# SCHEMATICS1.net
KiCad netlist of a schematic drawn in EasyEDA
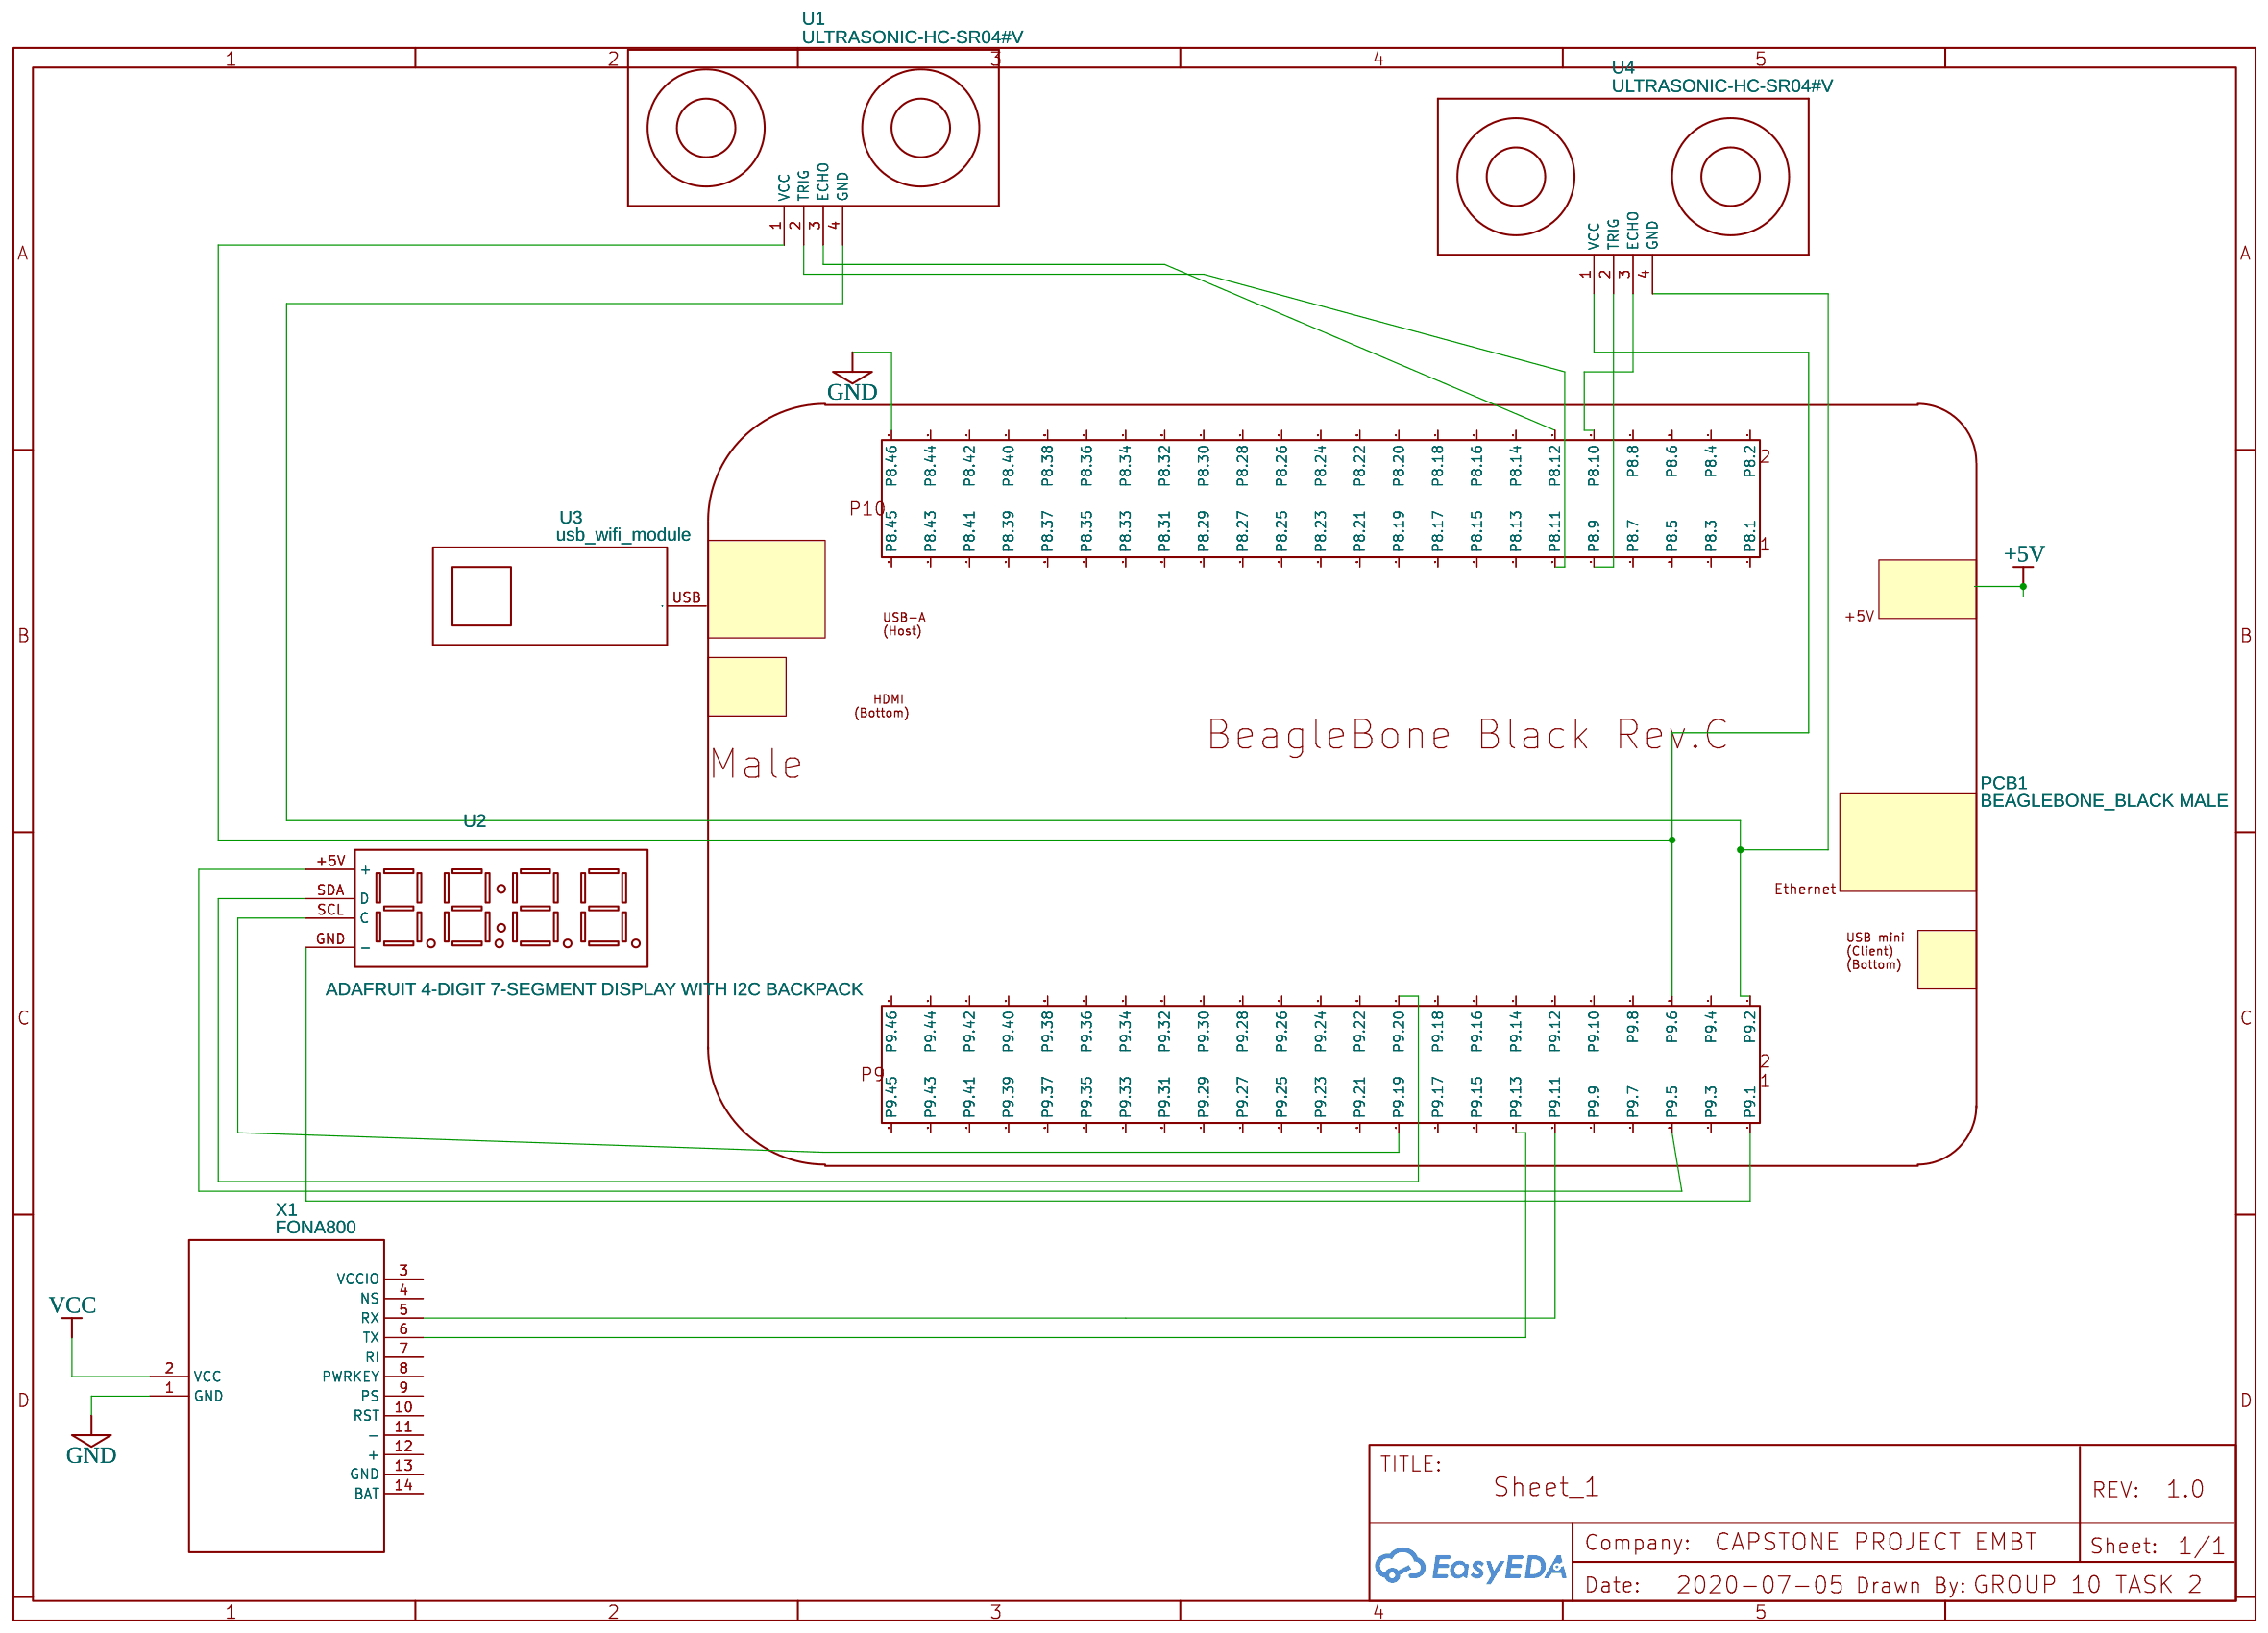
[diagram p0: schematic sheet]

(export (version "E")
  (design (tool "Eeschema 10.0.6"))
  (components
    (comp (ref "PCB1") (value "BEAGLEBONE_BLACK MALE") (libsource (lib "") (part "BEAGLEBONE_BLACK MALE")))
    (comp (ref "U1") (value "ULTRASONIC-HC-SR04#V") (libsource (lib "") (part "ULTRASONIC-HC-SR04#V")))
    (comp (ref "U2")
      (value "ADAFRUIT 4-DIGIT 7-SEGMENT DISPLAY WITH I2C BACKPACK")
      (libsource (lib "") (part "ADAFRUIT 4-DIGIT 7-SEGMENT DISPLAY WITH I2C BACKPACK"))
    )
    (comp (ref "U3")
      (value "usb_wifi_module")
      (fields (field (name "BOM_Manufacturer Part") "usb wifi module"))
      (libsource (lib "") (part "usb_wifi_module"))
    )
    (comp (ref "U4") (value "ULTRASONIC-HC-SR04#V") (libsource (lib "") (part "ULTRASONIC-HC-SR04#V")))
    (comp (ref "X1") (value "FONA800") (libsource (lib "") (part "FONA800")))
  )
  (nets
    (net (code "2") (name "GND") (class "Default")
      (node (ref "PCB1") (pin "P8.46") (pinfunction "P8.46_P8.46") (pintype "bidirectional"))
      (node (ref "X1") (pin "1") (pinfunction "GND_1") (pintype "unspecified"))
    )
    (net (code "3") (name "Net-(U1-ECHO)") (class "Default")
      (node (ref "PCB1") (pin "P8.12") (pinfunction "P8.12_P8.12") (pintype "bidirectional"))
      (node (ref "U1") (pin "3") (pinfunction "ECHO_3") (pintype "output"))
    )
    (net (code "4") (name "Net-(U1-GND)") (class "Default")
      (node (ref "PCB1") (pin "P9.2") (pinfunction "P9.2_P9.2") (pintype "bidirectional"))
      (node (ref "U1") (pin "4") (pinfunction "GND_4") (pintype "passive"))
      (node (ref "U4") (pin "4") (pinfunction "GND_4") (pintype "passive"))
    )
    (net (code "5") (name "Net-(U1-TRIG)") (class "Default")
      (node (ref "PCB1") (pin "P8.11") (pinfunction "P8.11_P8.11") (pintype "bidirectional"))
      (node (ref "U1") (pin "2") (pinfunction "TRIG_2") (pintype "input"))
    )
    (net (code "6") (name "Net-(U1-VCC)") (class "Default")
      (node (ref "PCB1") (pin "P9.6") (pinfunction "P9.6_P9.6") (pintype "bidirectional"))
      (node (ref "U1") (pin "1") (pinfunction "VCC_1") (pintype "passive"))
      (node (ref "U4") (pin "1") (pinfunction "VCC_1") (pintype "passive"))
    )
    (net (code "7") (name "Net-(U2-+)") (class "Default")
      (node (ref "PCB1") (pin "P9.5") (pinfunction "P9.5_P9.5") (pintype "bidirectional"))
      (node (ref "U2") (pin "+5V") (pinfunction "+_+5V") (pintype "unspecified"))
    )
    (net (code "8") (name "Net-(U2--)") (class "Default")
      (node (ref "PCB1") (pin "P9.1") (pinfunction "P9.1_P9.1") (pintype "bidirectional"))
      (node (ref "U2") (pin "GND") (pinfunction "-_GND") (pintype "unspecified"))
    )
    (net (code "9") (name "Net-(U2-C)") (class "Default")
      (node (ref "PCB1") (pin "P9.19") (pinfunction "P9.19_P9.19") (pintype "bidirectional"))
      (node (ref "U2") (pin "SCL") (pinfunction "C_SCL") (pintype "unspecified"))
    )
    (net (code "10") (name "Net-(U2-D)") (class "Default")
      (node (ref "PCB1") (pin "P9.20") (pinfunction "P9.20_P9.20") (pintype "bidirectional"))
      (node (ref "U2") (pin "SDA") (pinfunction "D_SDA") (pintype "unspecified"))
    )
    (net (code "11") (name "Net-(U4-ECHO)") (class "Default")
      (node (ref "PCB1") (pin "P8.10") (pinfunction "P8.10_P8.10") (pintype "bidirectional"))
      (node (ref "U4") (pin "3") (pinfunction "ECHO_3") (pintype "output"))
    )
    (net (code "12") (name "Net-(U4-TRIG)") (class "Default")
      (node (ref "PCB1") (pin "P8.9") (pinfunction "P8.9_P8.9") (pintype "bidirectional"))
      (node (ref "U4") (pin "2") (pinfunction "TRIG_2") (pintype "input"))
    )
    (net (code "13") (name "Net-(X1-RX)") (class "Default")
      (node (ref "PCB1") (pin "P9.11") (pinfunction "P9.11_P9.11") (pintype "bidirectional"))
      (node (ref "X1") (pin "5") (pinfunction "RX_5") (pintype "unspecified"))
    )
    (net (code "14") (name "Net-(X1-TX)") (class "Default")
      (node (ref "PCB1") (pin "P9.13") (pinfunction "P9.13_P9.13") (pintype "bidirectional"))
      (node (ref "X1") (pin "6") (pinfunction "TX_6") (pintype "unspecified"))
    )
    (net (code "15") (name "VCC") (class "Default")
      (node (ref "X1") (pin "2") (pinfunction "VCC_2") (pintype "unspecified"))
    )
    (net (code "16") (name "unconnected-(PCB1-PadP8.1)") (class "Default")
      (node (ref "PCB1") (pin "P8.1") (pinfunction "P8.1_P8.1") (pintype "bidirectional"))
    )
    (net (code "17") (name "unconnected-(PCB1-PadP8.2)") (class "Default")
      (node (ref "PCB1") (pin "P8.2") (pinfunction "P8.2_P8.2") (pintype "bidirectional"))
    )
    (net (code "18") (name "unconnected-(PCB1-PadP8.3)") (class "Default")
      (node (ref "PCB1") (pin "P8.3") (pinfunction "P8.3_P8.3") (pintype "bidirectional"))
    )
    (net (code "19") (name "unconnected-(PCB1-PadP8.4)") (class "Default")
      (node (ref "PCB1") (pin "P8.4") (pinfunction "P8.4_P8.4") (pintype "bidirectional"))
    )
    (net (code "20") (name "unconnected-(PCB1-PadP8.5)") (class "Default")
      (node (ref "PCB1") (pin "P8.5") (pinfunction "P8.5_P8.5") (pintype "bidirectional"))
    )
    (net (code "21") (name "unconnected-(PCB1-PadP8.6)") (class "Default")
      (node (ref "PCB1") (pin "P8.6") (pinfunction "P8.6_P8.6") (pintype "bidirectional"))
    )
    (net (code "22") (name "unconnected-(PCB1-PadP8.7)") (class "Default")
      (node (ref "PCB1") (pin "P8.7") (pinfunction "P8.7_P8.7") (pintype "bidirectional"))
    )
    (net (code "23") (name "unconnected-(PCB1-PadP8.8)") (class "Default")
      (node (ref "PCB1") (pin "P8.8") (pinfunction "P8.8_P8.8") (pintype "bidirectional"))
    )
    (net (code "24") (name "unconnected-(PCB1-PadP8.13)") (class "Default")
      (node (ref "PCB1") (pin "P8.13") (pinfunction "P8.13_P8.13") (pintype "bidirectional"))
    )
    (net (code "25") (name "unconnected-(PCB1-PadP8.14)") (class "Default")
      (node (ref "PCB1") (pin "P8.14") (pinfunction "P8.14_P8.14") (pintype "bidirectional"))
    )
    (net (code "26") (name "unconnected-(PCB1-PadP8.15)") (class "Default")
      (node (ref "PCB1") (pin "P8.15") (pinfunction "P8.15_P8.15") (pintype "bidirectional"))
    )
    (net (code "27") (name "unconnected-(PCB1-PadP8.16)") (class "Default")
      (node (ref "PCB1") (pin "P8.16") (pinfunction "P8.16_P8.16") (pintype "bidirectional"))
    )
    (net (code "28") (name "unconnected-(PCB1-PadP8.17)") (class "Default")
      (node (ref "PCB1") (pin "P8.17") (pinfunction "P8.17_P8.17") (pintype "bidirectional"))
    )
    (net (code "29") (name "unconnected-(PCB1-PadP8.18)") (class "Default")
      (node (ref "PCB1") (pin "P8.18") (pinfunction "P8.18_P8.18") (pintype "bidirectional"))
    )
    (net (code "30") (name "unconnected-(PCB1-PadP8.19)") (class "Default")
      (node (ref "PCB1") (pin "P8.19") (pinfunction "P8.19_P8.19") (pintype "bidirectional"))
    )
    (net (code "31") (name "unconnected-(PCB1-PadP8.20)") (class "Default")
      (node (ref "PCB1") (pin "P8.20") (pinfunction "P8.20_P8.20") (pintype "bidirectional"))
    )
    (net (code "32") (name "unconnected-(PCB1-PadP8.21)") (class "Default")
      (node (ref "PCB1") (pin "P8.21") (pinfunction "P8.21_P8.21") (pintype "bidirectional"))
    )
    (net (code "33") (name "unconnected-(PCB1-PadP8.22)") (class "Default")
      (node (ref "PCB1") (pin "P8.22") (pinfunction "P8.22_P8.22") (pintype "bidirectional"))
    )
    (net (code "34") (name "unconnected-(PCB1-PadP8.23)") (class "Default")
      (node (ref "PCB1") (pin "P8.23") (pinfunction "P8.23_P8.23") (pintype "bidirectional"))
    )
    (net (code "35") (name "unconnected-(PCB1-PadP8.24)") (class "Default")
      (node (ref "PCB1") (pin "P8.24") (pinfunction "P8.24_P8.24") (pintype "bidirectional"))
    )
    (net (code "36") (name "unconnected-(PCB1-PadP8.25)") (class "Default")
      (node (ref "PCB1") (pin "P8.25") (pinfunction "P8.25_P8.25") (pintype "bidirectional"))
    )
    (net (code "37") (name "unconnected-(PCB1-PadP8.26)") (class "Default")
      (node (ref "PCB1") (pin "P8.26") (pinfunction "P8.26_P8.26") (pintype "bidirectional"))
    )
    (net (code "38") (name "unconnected-(PCB1-PadP8.27)") (class "Default")
      (node (ref "PCB1") (pin "P8.27") (pinfunction "P8.27_P8.27") (pintype "bidirectional"))
    )
    (net (code "39") (name "unconnected-(PCB1-PadP8.28)") (class "Default")
      (node (ref "PCB1") (pin "P8.28") (pinfunction "P8.28_P8.28") (pintype "bidirectional"))
    )
    (net (code "40") (name "unconnected-(PCB1-PadP8.29)") (class "Default")
      (node (ref "PCB1") (pin "P8.29") (pinfunction "P8.29_P8.29") (pintype "bidirectional"))
    )
    (net (code "41") (name "unconnected-(PCB1-PadP8.30)") (class "Default")
      (node (ref "PCB1") (pin "P8.30") (pinfunction "P8.30_P8.30") (pintype "bidirectional"))
    )
    (net (code "42") (name "unconnected-(PCB1-PadP8.31)") (class "Default")
      (node (ref "PCB1") (pin "P8.31") (pinfunction "P8.31_P8.31") (pintype "bidirectional"))
    )
    (net (code "43") (name "unconnected-(PCB1-PadP8.32)") (class "Default")
      (node (ref "PCB1") (pin "P8.32") (pinfunction "P8.32_P8.32") (pintype "bidirectional"))
    )
    (net (code "44") (name "unconnected-(PCB1-PadP8.33)") (class "Default")
      (node (ref "PCB1") (pin "P8.33") (pinfunction "P8.33_P8.33") (pintype "bidirectional"))
    )
    (net (code "45") (name "unconnected-(PCB1-PadP8.34)") (class "Default")
      (node (ref "PCB1") (pin "P8.34") (pinfunction "P8.34_P8.34") (pintype "bidirectional"))
    )
    (net (code "46") (name "unconnected-(PCB1-PadP8.35)") (class "Default")
      (node (ref "PCB1") (pin "P8.35") (pinfunction "P8.35_P8.35") (pintype "bidirectional"))
    )
    (net (code "47") (name "unconnected-(PCB1-PadP8.36)") (class "Default")
      (node (ref "PCB1") (pin "P8.36") (pinfunction "P8.36_P8.36") (pintype "bidirectional"))
    )
    (net (code "48") (name "unconnected-(PCB1-PadP8.37)") (class "Default")
      (node (ref "PCB1") (pin "P8.37") (pinfunction "P8.37_P8.37") (pintype "bidirectional"))
    )
    (net (code "49") (name "unconnected-(PCB1-PadP8.38)") (class "Default")
      (node (ref "PCB1") (pin "P8.38") (pinfunction "P8.38_P8.38") (pintype "bidirectional"))
    )
    (net (code "50") (name "unconnected-(PCB1-PadP8.39)") (class "Default")
      (node (ref "PCB1") (pin "P8.39") (pinfunction "P8.39_P8.39") (pintype "bidirectional"))
    )
    (net (code "51") (name "unconnected-(PCB1-PadP8.40)") (class "Default")
      (node (ref "PCB1") (pin "P8.40") (pinfunction "P8.40_P8.40") (pintype "bidirectional"))
    )
    (net (code "52") (name "unconnected-(PCB1-PadP8.41)") (class "Default")
      (node (ref "PCB1") (pin "P8.41") (pinfunction "P8.41_P8.41") (pintype "bidirectional"))
    )
    (net (code "53") (name "unconnected-(PCB1-PadP8.42)") (class "Default")
      (node (ref "PCB1") (pin "P8.42") (pinfunction "P8.42_P8.42") (pintype "bidirectional"))
    )
    (net (code "54") (name "unconnected-(PCB1-PadP8.43)") (class "Default")
      (node (ref "PCB1") (pin "P8.43") (pinfunction "P8.43_P8.43") (pintype "bidirectional"))
    )
    (net (code "55") (name "unconnected-(PCB1-PadP8.44)") (class "Default")
      (node (ref "PCB1") (pin "P8.44") (pinfunction "P8.44_P8.44") (pintype "bidirectional"))
    )
    (net (code "56") (name "unconnected-(PCB1-PadP8.45)") (class "Default")
      (node (ref "PCB1") (pin "P8.45") (pinfunction "P8.45_P8.45") (pintype "bidirectional"))
    )
    (net (code "57") (name "unconnected-(PCB1-PadP9.3)") (class "Default")
      (node (ref "PCB1") (pin "P9.3") (pinfunction "P9.3_P9.3") (pintype "bidirectional"))
    )
    (net (code "58") (name "unconnected-(PCB1-PadP9.4)") (class "Default")
      (node (ref "PCB1") (pin "P9.4") (pinfunction "P9.4_P9.4") (pintype "bidirectional"))
    )
    (net (code "59") (name "unconnected-(PCB1-PadP9.7)") (class "Default")
      (node (ref "PCB1") (pin "P9.7") (pinfunction "P9.7_P9.7") (pintype "bidirectional"))
    )
    (net (code "60") (name "unconnected-(PCB1-PadP9.8)") (class "Default")
      (node (ref "PCB1") (pin "P9.8") (pinfunction "P9.8_P9.8") (pintype "bidirectional"))
    )
    (net (code "61") (name "unconnected-(PCB1-PadP9.9)") (class "Default")
      (node (ref "PCB1") (pin "P9.9") (pinfunction "P9.9_P9.9") (pintype "bidirectional"))
    )
    (net (code "62") (name "unconnected-(PCB1-PadP9.10)") (class "Default")
      (node (ref "PCB1") (pin "P9.10") (pinfunction "P9.10_P9.10") (pintype "bidirectional"))
    )
    (net (code "63") (name "unconnected-(PCB1-PadP9.12)") (class "Default")
      (node (ref "PCB1") (pin "P9.12") (pinfunction "P9.12_P9.12") (pintype "bidirectional"))
    )
    (net (code "64") (name "unconnected-(PCB1-PadP9.14)") (class "Default")
      (node (ref "PCB1") (pin "P9.14") (pinfunction "P9.14_P9.14") (pintype "bidirectional"))
    )
    (net (code "65") (name "unconnected-(PCB1-PadP9.15)") (class "Default")
      (node (ref "PCB1") (pin "P9.15") (pinfunction "P9.15_P9.15") (pintype "bidirectional"))
    )
    (net (code "66") (name "unconnected-(PCB1-PadP9.16)") (class "Default")
      (node (ref "PCB1") (pin "P9.16") (pinfunction "P9.16_P9.16") (pintype "bidirectional"))
    )
    (net (code "67") (name "unconnected-(PCB1-PadP9.17)") (class "Default")
      (node (ref "PCB1") (pin "P9.17") (pinfunction "P9.17_P9.17") (pintype "bidirectional"))
    )
    (net (code "68") (name "unconnected-(PCB1-PadP9.18)") (class "Default")
      (node (ref "PCB1") (pin "P9.18") (pinfunction "P9.18_P9.18") (pintype "bidirectional"))
    )
    (net (code "69") (name "unconnected-(PCB1-PadP9.21)") (class "Default")
      (node (ref "PCB1") (pin "P9.21") (pinfunction "P9.21_P9.21") (pintype "bidirectional"))
    )
    (net (code "70") (name "unconnected-(PCB1-PadP9.22)") (class "Default")
      (node (ref "PCB1") (pin "P9.22") (pinfunction "P9.22_P9.22") (pintype "bidirectional"))
    )
    (net (code "71") (name "unconnected-(PCB1-PadP9.23)") (class "Default")
      (node (ref "PCB1") (pin "P9.23") (pinfunction "P9.23_P9.23") (pintype "bidirectional"))
    )
    (net (code "72") (name "unconnected-(PCB1-PadP9.24)") (class "Default")
      (node (ref "PCB1") (pin "P9.24") (pinfunction "P9.24_P9.24") (pintype "bidirectional"))
    )
    (net (code "73") (name "unconnected-(PCB1-PadP9.25)") (class "Default")
      (node (ref "PCB1") (pin "P9.25") (pinfunction "P9.25_P9.25") (pintype "bidirectional"))
    )
    (net (code "74") (name "unconnected-(PCB1-PadP9.26)") (class "Default")
      (node (ref "PCB1") (pin "P9.26") (pinfunction "P9.26_P9.26") (pintype "bidirectional"))
    )
    (net (code "75") (name "unconnected-(PCB1-PadP9.27)") (class "Default")
      (node (ref "PCB1") (pin "P9.27") (pinfunction "P9.27_P9.27") (pintype "bidirectional"))
    )
    (net (code "76") (name "unconnected-(PCB1-PadP9.28)") (class "Default")
      (node (ref "PCB1") (pin "P9.28") (pinfunction "P9.28_P9.28") (pintype "bidirectional"))
    )
    (net (code "77") (name "unconnected-(PCB1-PadP9.29)") (class "Default")
      (node (ref "PCB1") (pin "P9.29") (pinfunction "P9.29_P9.29") (pintype "bidirectional"))
    )
    (net (code "78") (name "unconnected-(PCB1-PadP9.30)") (class "Default")
      (node (ref "PCB1") (pin "P9.30") (pinfunction "P9.30_P9.30") (pintype "bidirectional"))
    )
    (net (code "79") (name "unconnected-(PCB1-PadP9.31)") (class "Default")
      (node (ref "PCB1") (pin "P9.31") (pinfunction "P9.31_P9.31") (pintype "bidirectional"))
    )
    (net (code "80") (name "unconnected-(PCB1-PadP9.32)") (class "Default")
      (node (ref "PCB1") (pin "P9.32") (pinfunction "P9.32_P9.32") (pintype "bidirectional"))
    )
    (net (code "81") (name "unconnected-(PCB1-PadP9.33)") (class "Default")
      (node (ref "PCB1") (pin "P9.33") (pinfunction "P9.33_P9.33") (pintype "bidirectional"))
    )
    (net (code "82") (name "unconnected-(PCB1-PadP9.34)") (class "Default")
      (node (ref "PCB1") (pin "P9.34") (pinfunction "P9.34_P9.34") (pintype "bidirectional"))
    )
    (net (code "83") (name "unconnected-(PCB1-PadP9.35)") (class "Default")
      (node (ref "PCB1") (pin "P9.35") (pinfunction "P9.35_P9.35") (pintype "bidirectional"))
    )
    (net (code "84") (name "unconnected-(PCB1-PadP9.36)") (class "Default")
      (node (ref "PCB1") (pin "P9.36") (pinfunction "P9.36_P9.36") (pintype "bidirectional"))
    )
    (net (code "85") (name "unconnected-(PCB1-PadP9.37)") (class "Default")
      (node (ref "PCB1") (pin "P9.37") (pinfunction "P9.37_P9.37") (pintype "bidirectional"))
    )
    (net (code "86") (name "unconnected-(PCB1-PadP9.38)") (class "Default")
      (node (ref "PCB1") (pin "P9.38") (pinfunction "P9.38_P9.38") (pintype "bidirectional"))
    )
    (net (code "87") (name "unconnected-(PCB1-PadP9.39)") (class "Default")
      (node (ref "PCB1") (pin "P9.39") (pinfunction "P9.39_P9.39") (pintype "bidirectional"))
    )
    (net (code "88") (name "unconnected-(PCB1-PadP9.40)") (class "Default")
      (node (ref "PCB1") (pin "P9.40") (pinfunction "P9.40_P9.40") (pintype "bidirectional"))
    )
    (net (code "89") (name "unconnected-(PCB1-PadP9.41)") (class "Default")
      (node (ref "PCB1") (pin "P9.41") (pinfunction "P9.41_P9.41") (pintype "bidirectional"))
    )
    (net (code "90") (name "unconnected-(PCB1-PadP9.42)") (class "Default")
      (node (ref "PCB1") (pin "P9.42") (pinfunction "P9.42_P9.42") (pintype "bidirectional"))
    )
    (net (code "91") (name "unconnected-(PCB1-PadP9.43)") (class "Default")
      (node (ref "PCB1") (pin "P9.43") (pinfunction "P9.43_P9.43") (pintype "bidirectional"))
    )
    (net (code "92") (name "unconnected-(PCB1-PadP9.44)") (class "Default")
      (node (ref "PCB1") (pin "P9.44") (pinfunction "P9.44_P9.44") (pintype "bidirectional"))
    )
    (net (code "93") (name "unconnected-(PCB1-PadP9.45)") (class "Default")
      (node (ref "PCB1") (pin "P9.45") (pinfunction "P9.45_P9.45") (pintype "bidirectional"))
    )
    (net (code "94") (name "unconnected-(PCB1-PadP9.46)") (class "Default")
      (node (ref "PCB1") (pin "P9.46") (pinfunction "P9.46_P9.46") (pintype "bidirectional"))
    )
    (net (code "95") (name "unconnected-(U3-1-PadUSB)") (class "Default")
      (node (ref "U3") (pin "USB") (pinfunction "1_USB") (pintype "unspecified"))
    )
    (net (code "96") (name "unconnected-(X1-+-Pad12)") (class "Default")
      (node (ref "X1") (pin "12") (pinfunction "+_12") (pintype "unspecified"))
    )
    (net (code "97") (name "unconnected-(X1---Pad11)") (class "Default")
      (node (ref "X1") (pin "11") (pinfunction "-_11") (pintype "unspecified"))
    )
    (net (code "98") (name "unconnected-(X1-BAT-Pad14)") (class "Default")
      (node (ref "X1") (pin "14") (pinfunction "BAT_14") (pintype "unspecified"))
    )
    (net (code "99") (name "unconnected-(X1-GND-Pad13)") (class "Default")
      (node (ref "X1") (pin "13") (pinfunction "GND_13") (pintype "unspecified"))
    )
    (net (code "100") (name "unconnected-(X1-NS-Pad4)") (class "Default")
      (node (ref "X1") (pin "4") (pinfunction "NS_4") (pintype "unspecified"))
    )
    (net (code "101") (name "unconnected-(X1-PS-Pad9)") (class "Default")
      (node (ref "X1") (pin "9") (pinfunction "PS_9") (pintype "unspecified"))
    )
    (net (code "102") (name "unconnected-(X1-PWRKEY-Pad8)") (class "Default")
      (node (ref "X1") (pin "8") (pinfunction "PWRKEY_8") (pintype "unspecified"))
    )
    (net (code "103") (name "unconnected-(X1-RI-Pad7)") (class "Default")
      (node (ref "X1") (pin "7") (pinfunction "RI_7") (pintype "unspecified"))
    )
    (net (code "104") (name "unconnected-(X1-RST-Pad10)") (class "Default")
      (node (ref "X1") (pin "10") (pinfunction "RST_10") (pintype "unspecified"))
    )
    (net (code "105") (name "unconnected-(X1-VCCIO-Pad3)") (class "Default")
      (node (ref "X1") (pin "3") (pinfunction "VCCIO_3") (pintype "unspecified"))
    )
  )
)
